# POWER.net
KiCad netlist of a schematic drawn in Altium Designer
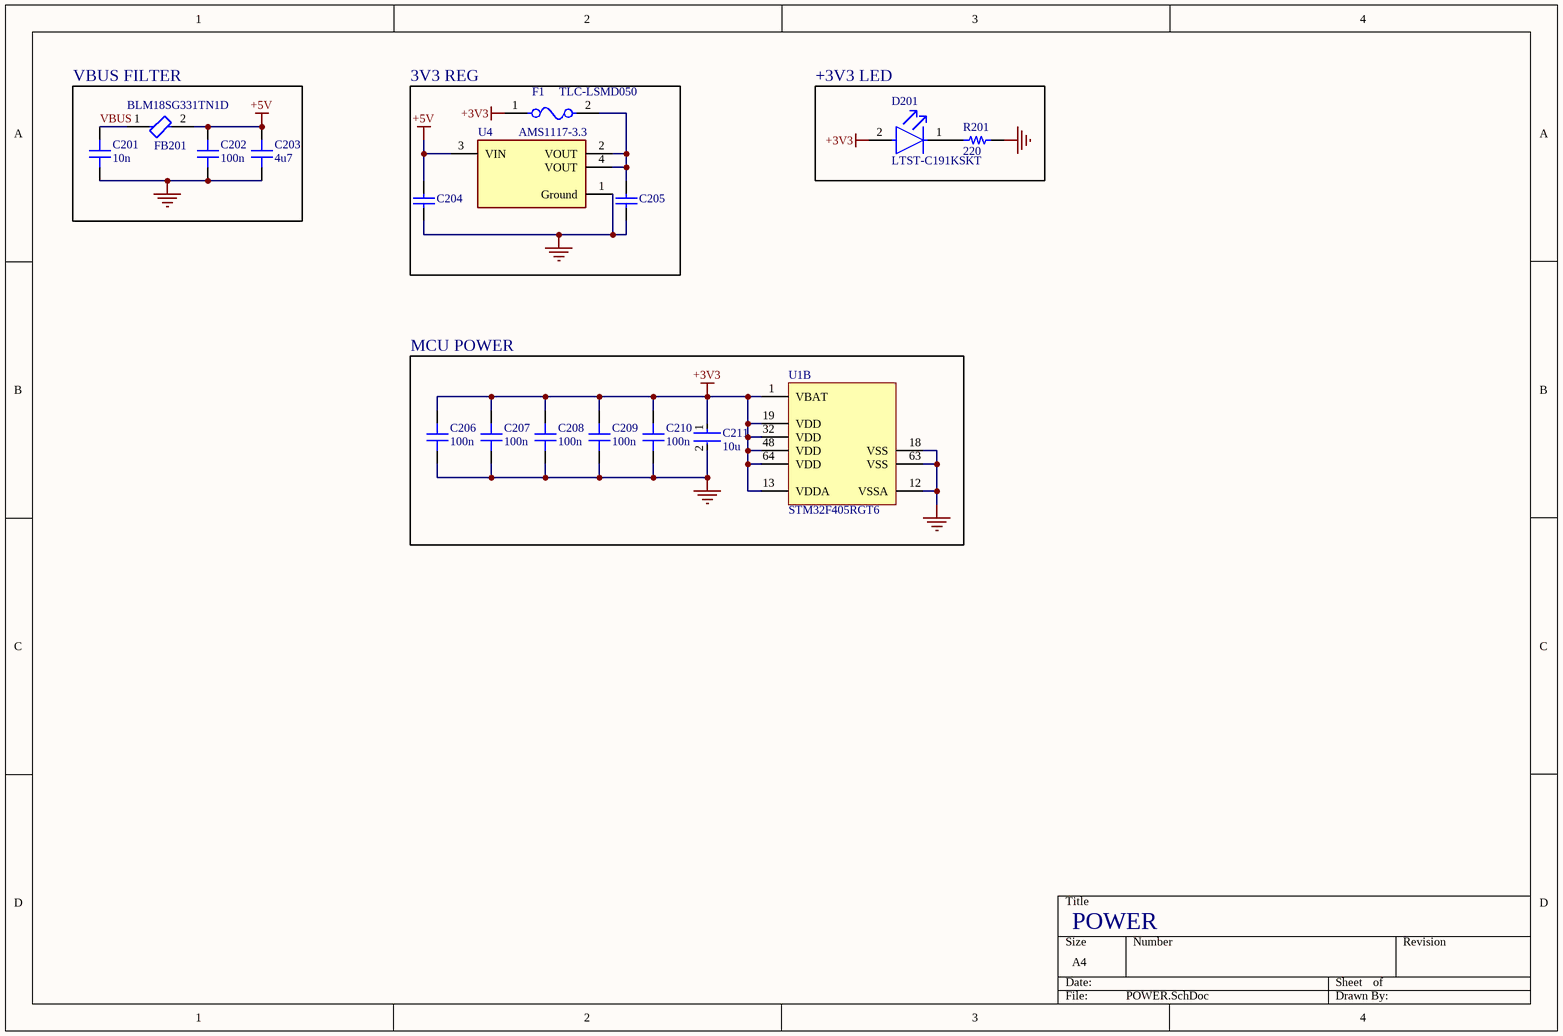
[diagram p0: POWER.SchDoc]

(export (version "E")
  (design (tool "Eeschema 10.0.6"))
  (components
    (comp (ref "C201")
      (value "10n")
      (footprint "CAP 0603_1608")
      (description "CAP CER 22UF 10V X5R 0603")
      (fields (field (name "PART NUMBER") "CL10A226MPCNUBE"))
      (libsource (lib "Celestial Altium Library - altium_library") (part "Capacitor"))
    )
    (comp (ref "C202")
      (value "100n")
      (footprint "CAP 0603_1608")
      (description "CAP CER 22UF 10V X5R 0603")
      (fields (field (name "PART NUMBER") "CL10A226MPCNUBE"))
      (libsource (lib "Celestial Altium Library - altium_library") (part "Capacitor"))
    )
    (comp (ref "C203")
      (value "4u7")
      (footprint "CAP 0603_1608")
      (description "CAP CER 22UF 10V X5R 0603")
      (fields (field (name "PART NUMBER") "CL10A226MPCNUBE"))
      (libsource (lib "Celestial Altium Library - altium_library") (part "Capacitor"))
    )
    (comp (ref "C204")
      (value "T529P226M010AAE200")
      (footprint "CAPC2013X100X55ML10T10")
      (fields (field (name "MANUFACTURER") "Kemet"))
      (libsource (lib "Altium Content Vault") (part "CAP"))
    )
    (comp (ref "C205")
      (value "T529P226M010AAE200")
      (footprint "CAPC2013X100X55ML10T10")
      (fields (field (name "MANUFACTURER") "Kemet"))
      (libsource (lib "Altium Content Vault") (part "CAP"))
    )
    (comp (ref "C206")
      (value "100n")
      (footprint "CAP 0402_1005")
      (description "CAP CER 100NF 10V X7R 0402")
      (fields
        (field (name "PART NUMBER") "CL05B104KP5VPNC")
        (field (name "MANUFACTURER") "Samsung Electro-Mechanics")
      )
      (libsource (lib "Celestial Altium Library - altium_library") (part "Capacitor"))
    )
    (comp (ref "C207")
      (value "100n")
      (footprint "CAP 0402_1005")
      (description "CAP CER 100NF 10V X7R 0402")
      (fields
        (field (name "PART NUMBER") "CL05B104KP5VPNC")
        (field (name "MANUFACTURER") "Samsung Electro-Mechanics")
      )
      (libsource (lib "Celestial Altium Library - altium_library") (part "Capacitor"))
    )
    (comp (ref "C208")
      (value "100n")
      (footprint "CAP 0402_1005")
      (description "CAP CER 100NF 10V X7R 0402")
      (fields
        (field (name "PART NUMBER") "CL05B104KP5VPNC")
        (field (name "MANUFACTURER") "Samsung Electro-Mechanics")
      )
      (libsource (lib "Celestial Altium Library - altium_library") (part "Capacitor"))
    )
    (comp (ref "C209")
      (value "100n")
      (footprint "CAP 0402_1005")
      (description "CAP CER 100NF 10V X7R 0402")
      (fields
        (field (name "PART NUMBER") "CL05B104KP5VPNC")
        (field (name "MANUFACTURER") "Samsung Electro-Mechanics")
      )
      (libsource (lib "Celestial Altium Library - altium_library") (part "Capacitor"))
    )
    (comp (ref "C210")
      (value "100n")
      (footprint "CAP 0402_1005")
      (description "CAP CER 100NF 10V X7R 0402")
      (fields
        (field (name "PART NUMBER") "CL05B104KP5VPNC")
        (field (name "MANUFACTURER") "Samsung Electro-Mechanics")
      )
      (libsource (lib "Celestial Altium Library - altium_library") (part "Capacitor"))
    )
    (comp (ref "C211")
      (value "10u")
      (footprint "FP-GRM21B-0_2-e0_2_0_7-IPC_B")
      (description "Chip Multilayer Ceramic Capacitors for General Purpose, 0805, 10uF, X7R, 15%, 10%, 25V")
      (libsource (lib "Altium Content Vault") (part "b4654b650e69147ec39a6b967a45e02"))
    )
    (comp (ref "D201")
      (value "LTST-C191KSKT")
      (footprint "FP-LTST-C191KSKT-MFG")
      (description "LED YELLOW CLEAR SMD")
      (libsource (lib "Altium Content Vault") (part "8706943c75ba83719d021d2fdc84c58"))
    )
    (comp (ref "F1")
      (value "TLC-LSMD050")
      (footprint "FP-2920L-MFG")
      (description "PTC RESET FUSE 15V 3A 2920")
      (fields
        (field (name "MANUFACTURER") "Littelfuse")
        (field (name "MANUFACTURER PART NUMBER") "2920L300/15DR")
      )
      (libsource (lib "Altium Content Vault") (part "5bcf9b9f640e542cf0359d10258e979"))
    )
    (comp (ref "FB201")
      (value "BLM18SG331TN1D")
      (footprint "FP-BLM18-0_15-t0_5-MFG")
      (description "Chip Ferrite Bead, 0603, 330Ω @ 100MHz, 25%, 0.07Ω, 1.5A")
      (fields (field (name "TOLERANCE") "25%"))
      (libsource (lib "Altium Content Vault") (part "5f30dd21d616792df468990f7003faa"))
    )
    (comp (ref "R201")
      (value "220")
      (footprint "RES 0402_1005")
      (description "RES 10K OHM 0.1% 1/10W 0402")
      (fields (field (name "PART NUMBER") "RP73PF1E10KBTD"))
      (libsource (lib "Celestial Altium Library - altium_library") (part "Resistor"))
    )
    (comp (ref "U1")
      (value "STM32F405RGT6")
      (footprint "STM-LQFP64_M")
      (fields (field (name "MANUFACTURER") "STMicroelectronics"))
      (libsource (lib "Altium Content Vault") (part "MC-ARM-STM32F4X5-SQ64"))
    )
    (comp (ref "U4")
      (value "AMS1117-3.3")
      (footprint "FP-AMS1117-IPC_C")
      (description "LDO Voltage Regulators 1A, 3.3V")
      (fields
        (field (name "OCTOPART") "https://octopart.com/ams1117-3.3-advanced+monolithic+systems-25899300")
        (field (name "MANUFACTURER") "Advanced Monolithic Systems")
      )
      (libsource (lib "Altium Content Vault") (part "8bdbb5f8e77002000e30dd2845d0354"))
    )
  )
  (nets
    (net (code "1") (name "+3V3") (class "Default")
      (node (ref "C206") (pin "2") (pinfunction "2_2") (pintype "passive"))
      (node (ref "C207") (pin "2") (pinfunction "2_2") (pintype "passive"))
      (node (ref "C208") (pin "2") (pinfunction "2_2") (pintype "passive"))
      (node (ref "C209") (pin "2") (pinfunction "2_2") (pintype "passive"))
      (node (ref "C210") (pin "2") (pinfunction "2_2") (pintype "passive"))
      (node (ref "C211") (pin "1") (pinfunction "1_1") (pintype "passive"))
      (node (ref "D201") (pin "2") (pinfunction "A_2") (pintype "passive"))
      (node (ref "F1") (pin "1") (pinfunction "1_1") (pintype "passive"))
      (node (ref "U1") (pin "1") (pinfunction "VBAT_1") (pintype "power_in"))
      (node (ref "U1") (pin "13") (pinfunction "VDDA_13") (pintype "power_in"))
      (node (ref "U1") (pin "19") (pinfunction "VDD_19") (pintype "power_in"))
      (node (ref "U1") (pin "32") (pinfunction "VDD_32") (pintype "power_in"))
      (node (ref "U1") (pin "48") (pinfunction "VDD_48") (pintype "power_in"))
      (node (ref "U1") (pin "64") (pinfunction "VDD_64") (pintype "power_in"))
    )
    (net (code "2") (name "+5V") (class "Default")
      (node (ref "C202") (pin "2") (pinfunction "2_2") (pintype "passive"))
      (node (ref "C203") (pin "2") (pinfunction "2_2") (pintype "passive"))
      (node (ref "C204") (pin "2") (pinfunction "2_2") (pintype "passive"))
      (node (ref "FB201") (pin "2") (pinfunction "2_2") (pintype "passive"))
      (node (ref "U4") (pin "3") (pinfunction "VIN_3") (pintype "power_in"))
    )
    (net (code "3") (name "/VBUS") (class "Default")
      (node (ref "C201") (pin "2") (pinfunction "2_2") (pintype "passive"))
      (node (ref "FB201") (pin "1") (pinfunction "1_1") (pintype "passive"))
    )
    (net (code "4") (name "GND") (class "Default")
      (node (ref "C201") (pin "1") (pinfunction "1_1") (pintype "passive"))
      (node (ref "C202") (pin "1") (pinfunction "1_1") (pintype "passive"))
      (node (ref "C203") (pin "1") (pinfunction "1_1") (pintype "passive"))
      (node (ref "C204") (pin "1") (pinfunction "1_1") (pintype "passive"))
      (node (ref "C205") (pin "1") (pinfunction "1_1") (pintype "passive"))
      (node (ref "C206") (pin "1") (pinfunction "1_1") (pintype "passive"))
      (node (ref "C207") (pin "1") (pinfunction "1_1") (pintype "passive"))
      (node (ref "C208") (pin "1") (pinfunction "1_1") (pintype "passive"))
      (node (ref "C209") (pin "1") (pinfunction "1_1") (pintype "passive"))
      (node (ref "C210") (pin "1") (pinfunction "1_1") (pintype "passive"))
      (node (ref "C211") (pin "2") (pinfunction "2_2") (pintype "passive"))
      (node (ref "R201") (pin "2") (pinfunction "2_2") (pintype "passive"))
      (node (ref "U1") (pin "12") (pinfunction "VSSA_12") (pintype "power_in"))
      (node (ref "U1") (pin "18") (pinfunction "VSS_18") (pintype "power_in"))
      (node (ref "U1") (pin "63") (pinfunction "VSS_63") (pintype "power_in"))
      (node (ref "U4") (pin "1") (pinfunction "Ground_1") (pintype "power_in"))
    )
    (net (code "5") (name "Net-(C205-Pad2)") (class "Default")
      (node (ref "C205") (pin "2") (pinfunction "2_2") (pintype "passive"))
      (node (ref "F1") (pin "2") (pinfunction "2_2") (pintype "passive"))
      (node (ref "U4") (pin "2") (pinfunction "VOUT_2") (pintype "passive"))
      (node (ref "U4") (pin "4") (pinfunction "VOUT_4") (pintype "passive"))
    )
    (net (code "6") (name "Net-(D201-C)") (class "Default")
      (node (ref "D201") (pin "1") (pinfunction "C_1") (pintype "passive"))
      (node (ref "R201") (pin "1") (pinfunction "1_1") (pintype "passive"))
    )
  )
)
